# AA_Sensor_Board_Reference_Design.net
KiCad netlist of a schematic drawn in EAGLE
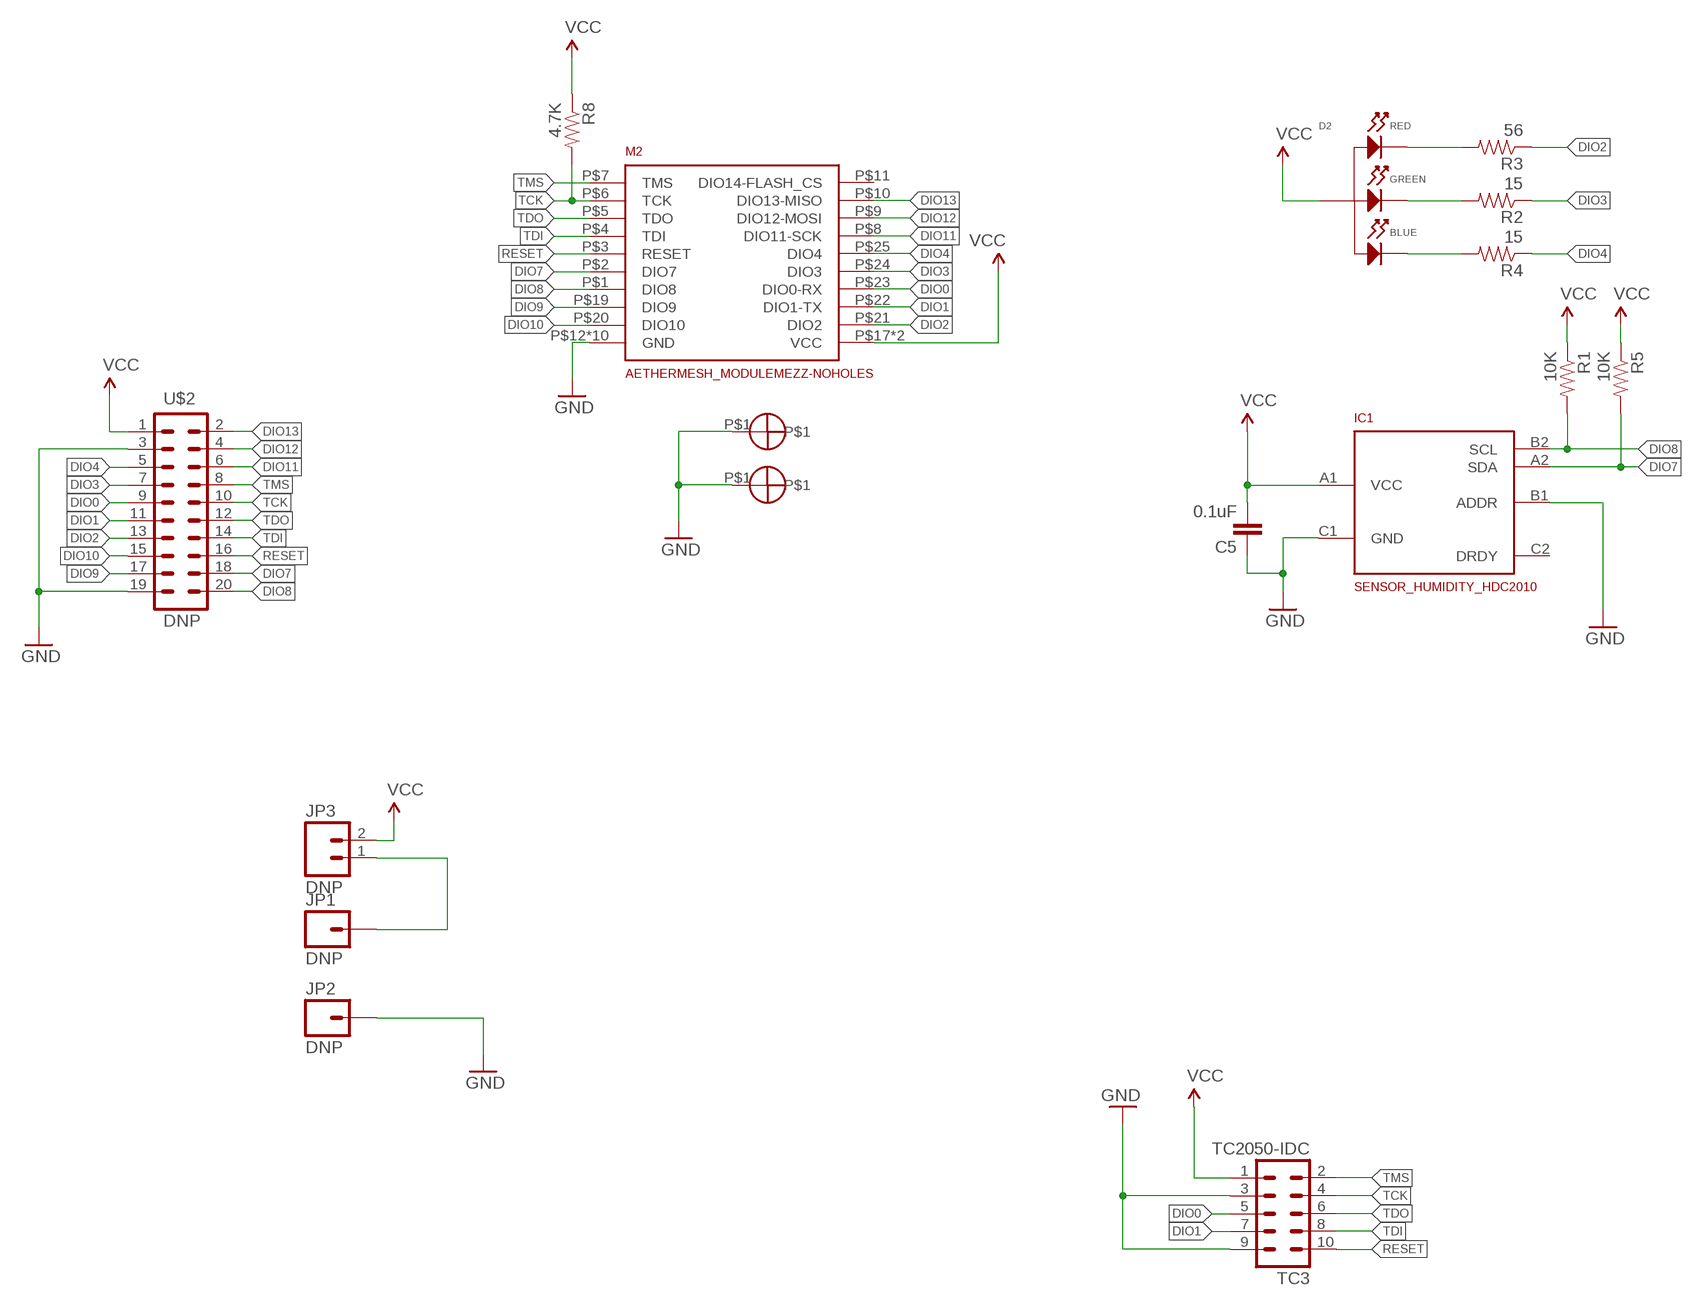
[diagram p0: schematic, sheet 1]

(export (version "E")
  (design (tool "Eeschema 10.0.6"))
  (components
    (comp (ref "C5")
      (value "0.1uF")
      (footprint "eagle-import:C0402")
      (libsource (lib "eagle-import") (part "CAPC0402"))
    )
    (comp (ref "D2")
      (value "LED_RGB_CA_PLCC4")
      (footprint "eagle-import:PLCC4")
      (fields (field (name "MFG#") "MF-LED-3228-RGB"))
      (libsource (lib "eagle-import") (part "LED_RGB_CA_PLCC4"))
    )
    (comp (ref "IC1")
      (value "SENSOR_HUMIDITY_HDC2010")
      (footprint "eagle-import:HDC2010")
      (libsource (lib "eagle-import") (part "SENSOR_HUMIDITY_HDC2010"))
    )
    (comp (ref "JP1")
      (value "DNP")
      (footprint "eagle-import:1X01_3.5X.75_BATT_SLOT")
      (libsource (lib "eagle-import") (part "M01BAT_SLOT"))
    )
    (comp (ref "JP2")
      (value "DNP")
      (footprint "eagle-import:1X01_3.5X.75_BATT_SLOT")
      (libsource (lib "eagle-import") (part "M01BAT_SLOT"))
    )
    (comp (ref "JP3")
      (value "DNP")
      (footprint "eagle-import:1X02_LOCK")
      (libsource (lib "eagle-import") (part "M02LOCK"))
    )
    (comp (ref "M2")
      (value "AETHERMESH_MODULEMEZZ-NOHOLES")
      (footprint "eagle-import:AETHERMESH_MEZZ_MOUNT_NOHOLES")
      (libsource (lib "eagle-import") (part "AETHERMESH_MODULEMEZZ-NOHOLES"))
    )
    (comp (ref "R1")
      (value "10K")
      (footprint "eagle-import:R0402")
      (libsource (lib "eagle-import") (part "RESISTORR0402"))
    )
    (comp (ref "R2")
      (value "15")
      (footprint "eagle-import:R0402")
      (libsource (lib "eagle-import") (part "RESISTORR0402"))
    )
    (comp (ref "R3")
      (value "56")
      (footprint "eagle-import:R0402")
      (libsource (lib "eagle-import") (part "RESISTORR0402"))
    )
    (comp (ref "R4")
      (value "15")
      (footprint "eagle-import:R0402")
      (libsource (lib "eagle-import") (part "RESISTORR0402"))
    )
    (comp (ref "R5")
      (value "10K")
      (footprint "eagle-import:R0402")
      (libsource (lib "eagle-import") (part "RESISTORR0402"))
    )
    (comp (ref "R8")
      (value "4.7K")
      (footprint "eagle-import:R0402")
      (libsource (lib "eagle-import") (part "RESISTORR0402"))
    )
    (comp (ref "S3")
      (value "STANDOFFWURTH")
      (footprint "eagle-import:STANDOFF_WURTH_9774040243R")
      (libsource (lib "eagle-import") (part "STANDOFFWURTH"))
    )
    (comp (ref "S4")
      (value "STANDOFFWURTH")
      (footprint "eagle-import:STANDOFF_WURTH_9774040243R")
      (libsource (lib "eagle-import") (part "STANDOFFWURTH"))
    )
    (comp (ref "TC3")
      (value "TC2050-IDC")
      (footprint "eagle-import:TC2050-IDC")
      (libsource (lib "eagle-import") (part "TC2050-IDC"))
    )
    (comp (ref "U$2")
      (value "DNP")
      (footprint "eagle-import:2X10_LOCK")
      (libsource (lib "eagle-import") (part "M10X22X10_LOCK"))
    )
  )
  (nets
    (net (code "1") (name "DIO0") (class "Default")
      (node (ref "M2") (pin "P$23") (pinfunction "DIO0-RX_P$23") (pintype "bidirectional"))
      (node (ref "TC3") (pin "5") (pinfunction "5_5") (pintype "passive"))
      (node (ref "U$2") (pin "9") (pinfunction "9_9") (pintype "passive"))
    )
    (net (code "2") (name "DIO1") (class "Default")
      (node (ref "M2") (pin "P$22") (pinfunction "DIO1-TX_P$22") (pintype "bidirectional"))
      (node (ref "TC3") (pin "7") (pinfunction "7_7") (pintype "passive"))
      (node (ref "U$2") (pin "11") (pinfunction "11_11") (pintype "passive"))
    )
    (net (code "3") (name "DIO2") (class "Default")
      (node (ref "M2") (pin "P$21") (pinfunction "DIO2_P$21") (pintype "bidirectional"))
      (node (ref "R3") (pin "P$1") (pinfunction "1_P$1") (pintype "passive"))
      (node (ref "U$2") (pin "13") (pinfunction "13_13") (pintype "passive"))
    )
    (net (code "4") (name "DIO3") (class "Default")
      (node (ref "M2") (pin "P$24") (pinfunction "DIO3_P$24") (pintype "bidirectional"))
      (node (ref "R2") (pin "P$1") (pinfunction "1_P$1") (pintype "passive"))
      (node (ref "U$2") (pin "7") (pinfunction "7_7") (pintype "passive"))
    )
    (net (code "5") (name "DIO4") (class "Default")
      (node (ref "M2") (pin "P$25") (pinfunction "DIO4_P$25") (pintype "bidirectional"))
      (node (ref "R4") (pin "P$1") (pinfunction "1_P$1") (pintype "passive"))
      (node (ref "U$2") (pin "5") (pinfunction "5_5") (pintype "passive"))
    )
    (net (code "6") (name "DIO7") (class "Default")
      (node (ref "IC1") (pin "A2") (pinfunction "SDA_A2") (pintype "bidirectional"))
      (node (ref "M2") (pin "P$2") (pinfunction "DIO7_P$2") (pintype "bidirectional"))
      (node (ref "R5") (pin "P$2") (pinfunction "2_P$2") (pintype "passive"))
      (node (ref "U$2") (pin "18") (pinfunction "18_18") (pintype "passive"))
    )
    (net (code "7") (name "DIO8") (class "Default")
      (node (ref "IC1") (pin "B2") (pinfunction "SCL_B2") (pintype "bidirectional"))
      (node (ref "M2") (pin "P$1") (pinfunction "DIO8_P$1") (pintype "bidirectional"))
      (node (ref "R1") (pin "P$2") (pinfunction "2_P$2") (pintype "passive"))
      (node (ref "U$2") (pin "20") (pinfunction "20_20") (pintype "passive"))
    )
    (net (code "8") (name "DIO9") (class "Default")
      (node (ref "M2") (pin "P$19") (pinfunction "DIO9_P$19") (pintype "bidirectional"))
      (node (ref "U$2") (pin "17") (pinfunction "17_17") (pintype "passive"))
    )
    (net (code "9") (name "DIO10") (class "Default")
      (node (ref "M2") (pin "P$20") (pinfunction "DIO10_P$20") (pintype "bidirectional"))
      (node (ref "U$2") (pin "15") (pinfunction "15_15") (pintype "passive"))
    )
    (net (code "10") (name "DIO11") (class "Default")
      (node (ref "M2") (pin "P$8") (pinfunction "DIO11-SCK_P$8") (pintype "bidirectional"))
      (node (ref "U$2") (pin "6") (pinfunction "6_6") (pintype "passive"))
    )
    (net (code "11") (name "DIO12") (class "Default")
      (node (ref "M2") (pin "P$9") (pinfunction "DIO12-MOSI_P$9") (pintype "bidirectional"))
      (node (ref "U$2") (pin "4") (pinfunction "4_4") (pintype "passive"))
    )
    (net (code "12") (name "DIO13") (class "Default")
      (node (ref "M2") (pin "P$10") (pinfunction "DIO13-MISO_P$10") (pintype "bidirectional"))
      (node (ref "U$2") (pin "2") (pinfunction "2_2") (pintype "passive"))
    )
    (net (code "13") (name "GND") (class "Default")
      (node (ref "C5") (pin "P$1") (pinfunction "1_P$1") (pintype "passive"))
      (node (ref "IC1") (pin "B1") (pinfunction "ADDR_B1") (pintype "bidirectional"))
      (node (ref "IC1") (pin "C1") (pinfunction "GND_C1") (pintype "bidirectional"))
      (node (ref "JP2") (pin "P$1") (pinfunction "1_P$1") (pintype "passive"))
      (node (ref "M2") (pin "P$12") (pinfunction "GND_P$12") (pintype "bidirectional"))
      (node (ref "M2") (pin "P$13") (pinfunction "GND_P$13") (pintype "bidirectional"))
      (node (ref "M2") (pin "P$14") (pinfunction "GND_P$14") (pintype "bidirectional"))
      (node (ref "M2") (pin "P$15") (pinfunction "GND_P$15") (pintype "bidirectional"))
      (node (ref "M2") (pin "P$16") (pinfunction "GND_P$16") (pintype "bidirectional"))
      (node (ref "M2") (pin "P$26") (pinfunction "GND_P$26") (pintype "bidirectional"))
      (node (ref "M2") (pin "P$27") (pinfunction "GND_P$27") (pintype "bidirectional"))
      (node (ref "M2") (pin "P$28") (pinfunction "GND_P$28") (pintype "bidirectional"))
      (node (ref "M2") (pin "P$29") (pinfunction "GND_P$29") (pintype "bidirectional"))
      (node (ref "M2") (pin "P$30") (pinfunction "GND_P$30") (pintype "bidirectional"))
      (node (ref "S3") (pin "P$1") (pinfunction "P$1_P$1") (pintype "bidirectional"))
      (node (ref "S4") (pin "P$1") (pinfunction "P$1_P$1") (pintype "bidirectional"))
      (node (ref "TC3") (pin "3") (pinfunction "3_3") (pintype "passive"))
      (node (ref "TC3") (pin "9") (pinfunction "9_9") (pintype "passive"))
      (node (ref "U$2") (pin "19") (pinfunction "19_19") (pintype "passive"))
      (node (ref "U$2") (pin "3") (pinfunction "3_3") (pintype "passive"))
    )
    (net (code "14") (name "Net-(D2-CATHODE_BLUE)") (class "Default")
      (node (ref "D2") (pin "P$4") (pinfunction "CATHODE_BLUE_P$4") (pintype "power_in"))
      (node (ref "R4") (pin "P$2") (pinfunction "2_P$2") (pintype "passive"))
    )
    (net (code "15") (name "Net-(D2-CATHODE_GREEN)") (class "Default")
      (node (ref "D2") (pin "P$3") (pinfunction "CATHODE_GREEN_P$3") (pintype "power_in"))
      (node (ref "R2") (pin "P$2") (pinfunction "2_P$2") (pintype "passive"))
    )
    (net (code "16") (name "Net-(D2-CATHODE_RED)") (class "Default")
      (node (ref "D2") (pin "P$2") (pinfunction "CATHODE_RED_P$2") (pintype "power_in"))
      (node (ref "R3") (pin "P$2") (pinfunction "2_P$2") (pintype "passive"))
    )
    (net (code "17") (name "Net-(JP1-1)") (class "Default")
      (node (ref "JP1") (pin "P$1") (pinfunction "1_P$1") (pintype "passive"))
      (node (ref "JP3") (pin "1") (pinfunction "1_1") (pintype "passive"))
    )
    (net (code "18") (name "RESET") (class "Default")
      (node (ref "M2") (pin "P$3") (pinfunction "RESET_P$3") (pintype "bidirectional"))
      (node (ref "TC3") (pin "10") (pinfunction "10_10") (pintype "passive"))
      (node (ref "U$2") (pin "16") (pinfunction "16_16") (pintype "passive"))
    )
    (net (code "19") (name "TCK") (class "Default")
      (node (ref "M2") (pin "P$6") (pinfunction "TCK_P$6") (pintype "bidirectional"))
      (node (ref "R8") (pin "P$2") (pinfunction "2_P$2") (pintype "passive"))
      (node (ref "TC3") (pin "4") (pinfunction "4_4") (pintype "passive"))
      (node (ref "U$2") (pin "10") (pinfunction "10_10") (pintype "passive"))
    )
    (net (code "20") (name "TDI") (class "Default")
      (node (ref "M2") (pin "P$4") (pinfunction "TDI_P$4") (pintype "bidirectional"))
      (node (ref "TC3") (pin "8") (pinfunction "8_8") (pintype "passive"))
      (node (ref "U$2") (pin "14") (pinfunction "14_14") (pintype "passive"))
    )
    (net (code "21") (name "TDO") (class "Default")
      (node (ref "M2") (pin "P$5") (pinfunction "TDO_P$5") (pintype "bidirectional"))
      (node (ref "TC3") (pin "6") (pinfunction "6_6") (pintype "passive"))
      (node (ref "U$2") (pin "12") (pinfunction "12_12") (pintype "passive"))
    )
    (net (code "22") (name "TMS") (class "Default")
      (node (ref "M2") (pin "P$7") (pinfunction "TMS_P$7") (pintype "bidirectional"))
      (node (ref "TC3") (pin "2") (pinfunction "2_2") (pintype "passive"))
      (node (ref "U$2") (pin "8") (pinfunction "8_8") (pintype "passive"))
    )
    (net (code "23") (name "VCC") (class "Default")
      (node (ref "C5") (pin "P$2") (pinfunction "2_P$2") (pintype "passive"))
      (node (ref "D2") (pin "P$1") (pinfunction "ANODE_P$1") (pintype "power_in"))
      (node (ref "IC1") (pin "A1") (pinfunction "VCC_A1") (pintype "bidirectional"))
      (node (ref "JP3") (pin "2") (pinfunction "2_2") (pintype "passive"))
      (node (ref "M2") (pin "P$17") (pinfunction "VCC_P$17") (pintype "bidirectional"))
      (node (ref "M2") (pin "P$18") (pinfunction "VCC_P$18") (pintype "bidirectional"))
      (node (ref "R1") (pin "P$1") (pinfunction "1_P$1") (pintype "passive"))
      (node (ref "R5") (pin "P$1") (pinfunction "1_P$1") (pintype "passive"))
      (node (ref "R8") (pin "P$1") (pinfunction "1_P$1") (pintype "passive"))
      (node (ref "TC3") (pin "1") (pinfunction "1_1") (pintype "passive"))
      (node (ref "U$2") (pin "1") (pinfunction "1_1") (pintype "passive"))
    )
    (net (code "24") (name "unconnected-(IC1-DRDY-PadC2)") (class "Default")
      (node (ref "IC1") (pin "C2") (pinfunction "DRDY_C2") (pintype "bidirectional"))
    )
    (net (code "25") (name "unconnected-(M2-DIO14-FLASH_CS-PadP$11)") (class "Default")
      (node (ref "M2") (pin "P$11") (pinfunction "DIO14-FLASH_CS_P$11") (pintype "bidirectional"))
    )
  )
)
